# design.net
KiCad netlist of a schematic drawn in Altium Designer
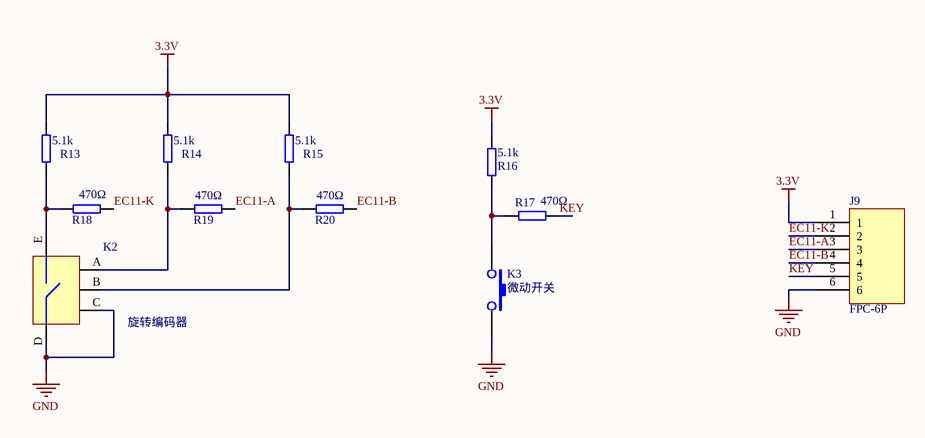
[diagram p0: 按钮小板.SchDoc]

(export (version "E")
  (design (tool "Eeschema 10.0.6"))
  (components
    (comp (ref "J9") (value "FPC-6P") (footprint "FPC0.5-WT-6P") (libsource (lib "定位手表") (part "FPC-6P")))
    (comp (ref "K2") (value "旋转编码器") (footprint "旋转编码器") (libsource (lib "定位手表") (part "选装编码器")))
    (comp (ref "K3") (value "微动开关") (footprint "轻触开关") (libsource (lib "定位手表") (part "微动开关")))
    (comp (ref "R13")
      (value "5.1k")
      (footprint "0603-RES")
      (description "电阻")
      (libsource (lib "定位手表") (part "电阻"))
    )
    (comp (ref "R14")
      (value "5.1k")
      (footprint "0603-RES")
      (description "电阻")
      (libsource (lib "定位手表") (part "电阻"))
    )
    (comp (ref "R15")
      (value "5.1k")
      (footprint "0603-RES")
      (description "电阻")
      (libsource (lib "定位手表") (part "电阻"))
    )
    (comp (ref "R16")
      (value "5.1k")
      (footprint "0603-RES")
      (description "电阻")
      (libsource (lib "定位手表") (part "电阻"))
    )
    (comp (ref "R17")
      (value "470Ω")
      (footprint "0603-RES")
      (description "电阻")
      (libsource (lib "定位手表") (part "电阻"))
    )
    (comp (ref "R18")
      (value "470Ω")
      (footprint "0603-RES")
      (description "电阻")
      (libsource (lib "定位手表") (part "电阻"))
    )
    (comp (ref "R19")
      (value "470Ω")
      (footprint "0603-RES")
      (description "电阻")
      (libsource (lib "定位手表") (part "电阻"))
    )
    (comp (ref "R20")
      (value "470Ω")
      (footprint "0603-RES")
      (description "电阻")
      (libsource (lib "定位手表") (part "电阻"))
    )
  )
  (nets
    (net (code "1") (name "/EC11-A") (class "Default")
      (node (ref "J9") (pin "3") (pinfunction "3_3") (pintype "passive"))
      (node (ref "R19") (pin "2") (pinfunction "2_2") (pintype "passive"))
    )
    (net (code "2") (name "/EC11-B") (class "Default")
      (node (ref "J9") (pin "4") (pinfunction "4_4") (pintype "passive"))
      (node (ref "R20") (pin "2") (pinfunction "2_2") (pintype "passive"))
    )
    (net (code "3") (name "/EC11-K") (class "Default")
      (node (ref "J9") (pin "2") (pinfunction "2_2") (pintype "passive"))
      (node (ref "R18") (pin "2") (pinfunction "2_2") (pintype "passive"))
    )
    (net (code "4") (name "/KEY") (class "Default")
      (node (ref "J9") (pin "5") (pinfunction "5_5") (pintype "passive"))
      (node (ref "R17") (pin "2") (pinfunction "2_2") (pintype "passive"))
    )
    (net (code "5") (name "3.3V") (class "Default")
      (node (ref "J9") (pin "1") (pinfunction "1_1") (pintype "passive"))
      (node (ref "R13") (pin "1") (pinfunction "1_1") (pintype "passive"))
      (node (ref "R14") (pin "1") (pinfunction "1_1") (pintype "passive"))
      (node (ref "R15") (pin "1") (pinfunction "1_1") (pintype "passive"))
      (node (ref "R16") (pin "2") (pinfunction "2_2") (pintype "passive"))
    )
    (net (code "6") (name "GND") (class "Default")
      (node (ref "J9") (pin "6") (pinfunction "6_6") (pintype "passive"))
      (node (ref "K2") (pin "C") (pinfunction "C_C") (pintype "passive"))
      (node (ref "K2") (pin "D") (pinfunction "D_D") (pintype "passive"))
      (node (ref "K3") (pin "2") (pinfunction "2_2") (pintype "passive"))
    )
    (net (code "7") (name "Net-(K2-PadA)") (class "Default")
      (node (ref "K2") (pin "A") (pinfunction "A_A") (pintype "passive"))
      (node (ref "R14") (pin "2") (pinfunction "2_2") (pintype "passive"))
      (node (ref "R19") (pin "1") (pinfunction "1_1") (pintype "passive"))
    )
    (net (code "8") (name "Net-(K2-PadB)") (class "Default")
      (node (ref "K2") (pin "B") (pinfunction "B_B") (pintype "passive"))
      (node (ref "R15") (pin "2") (pinfunction "2_2") (pintype "passive"))
      (node (ref "R20") (pin "1") (pinfunction "1_1") (pintype "passive"))
    )
    (net (code "9") (name "Net-(K2-PadE)") (class "Default")
      (node (ref "K2") (pin "E") (pinfunction "E_E") (pintype "passive"))
      (node (ref "R13") (pin "2") (pinfunction "2_2") (pintype "passive"))
      (node (ref "R18") (pin "1") (pinfunction "1_1") (pintype "passive"))
    )
    (net (code "10") (name "Net-(K3-Pad1)") (class "Default")
      (node (ref "K3") (pin "1") (pinfunction "1_1") (pintype "passive"))
      (node (ref "R16") (pin "1") (pinfunction "1_1") (pintype "passive"))
      (node (ref "R17") (pin "1") (pinfunction "1_1") (pintype "passive"))
    )
  )
)
